# Badge_Cig.net
KiCad netlist of a schematic drawn in Altium Designer
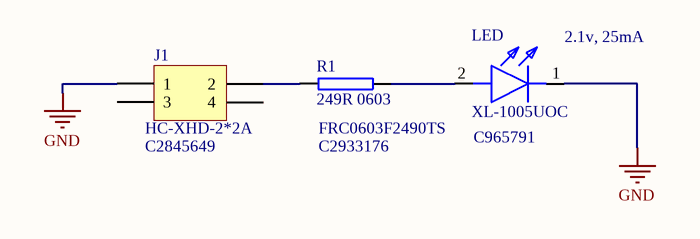
[diagram p0: Badge_Cig.SchDoc]

(export (version "E")
  (design (tool "Eeschema 10.0.6"))
  (components
    (comp (ref "J1")
      (value "HC-XHD-2*2A")
      (footprint "HDR2X2_AUT")
      (description "Header, 2-Pin, Dual row, 2.54mm Pitch, Straight")
      (libsource (lib "Connectors") (part "HDR2X2"))
    )
    (comp (ref "LED")
      (value "XL-1005UOC")
      (footprint "SamacSys:150040GS73240")
      (description "LED")
      (fields
        (field (name "MANUFACTURER_PART_NUMBER") "150040GS73240")
        (field (name "MOUSER PART NUMBER") "710-150040GS73240")
      )
      (libsource (lib "*") (part "150040GS73240"))
    )
    (comp (ref "R1")
      (value "249R 0603")
      (footprint "Res_0603")
      (description "Resistor, SMD, 1206")
      (libsource (lib "Resistors and Capacitors") (part "Resistor 1206"))
    )
  )
  (nets
    (net (code "1") (name "GND") (class "Default")
      (node (ref "J1") (pin "1") (pinfunction "1_1") (pintype "passive"))
      (node (ref "LED") (pin "1") (pinfunction "K_1") (pintype "passive"))
    )
    (net (code "2") (name "Net-(J1-Pad2)") (class "Default")
      (node (ref "J1") (pin "2") (pinfunction "2_2") (pintype "passive"))
      (node (ref "R1") (pin "1") (pinfunction "1_1") (pintype "passive"))
    )
    (net (code "3") (name "Net-(LED-A)") (class "Default")
      (node (ref "LED") (pin "2") (pinfunction "A_2") (pintype "passive"))
      (node (ref "R1") (pin "2") (pinfunction "2_2") (pintype "passive"))
    )
    (net (code "4") (name "unconnected-(J1-Pad3)") (class "Default")
      (node (ref "J1") (pin "3") (pinfunction "3_3") (pintype "passive"))
    )
    (net (code "5") (name "unconnected-(J1-Pad4)") (class "Default")
      (node (ref "J1") (pin "4") (pinfunction "4_4") (pintype "passive"))
    )
  )
)
